# 5V_Buck_Boost_Converter.net
KiCad netlist of a schematic drawn in Altium Designer
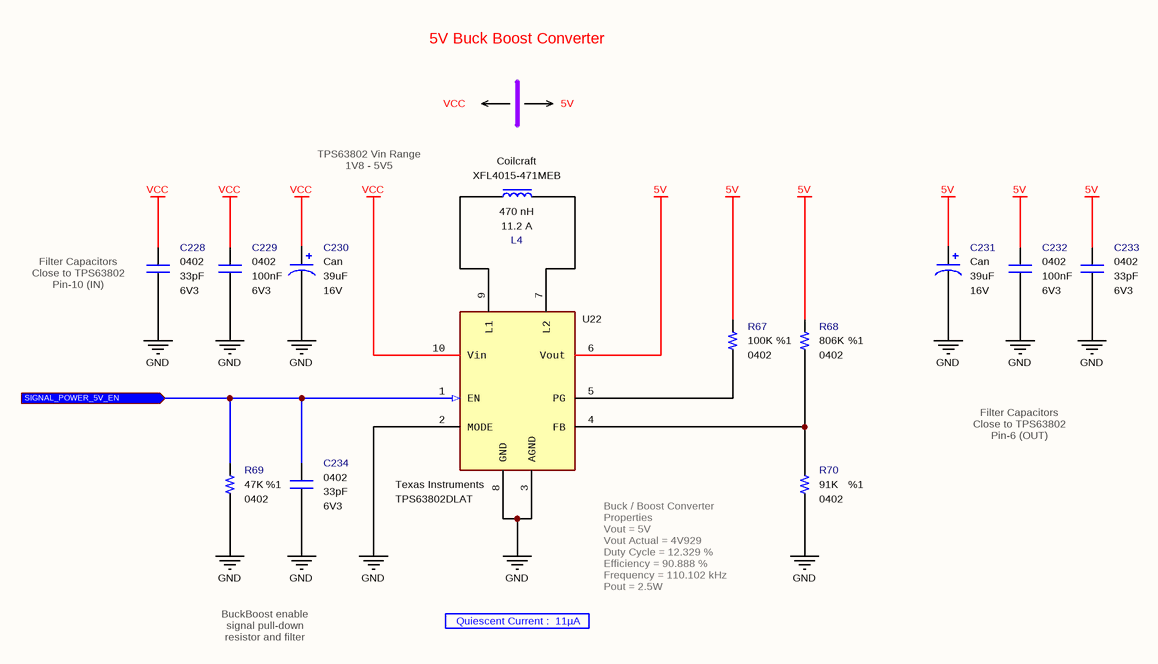
[diagram p0: 5V Buck Boost Converter.SchDoc]

(export (version "E")
  (design (tool "Eeschema 10.0.6"))
  (components
    (comp (ref "C228")
      (value "33pF")
      (footprint "CAPACITOR_0402")
      (description "Capacitor - 33pF [0402] (Ceramic)")
      (fields
        (field (name "TOLERANCE") "10%")
        (field (name "CASE") "0402")
        (field (name "VOLTAGE") "6V3")
        (field (name "MANUFACTURER PART NUMBER") "C0402C330J9RACAUTO")
      )
      (libsource (lib "Ovoo_Library") (part "Capacitor - 33pF [0402-6V3]"))
    )
    (comp (ref "C229")
      (value "100nF")
      (footprint "CAPACITOR_0402")
      (description "Capacitor - 100nF [0402-6V3] (Ceramic)")
      (fields
        (field (name "CASE") "0402")
        (field (name "TOLERANCE") "%10")
        (field (name "VOLTAGE") "6V3")
        (field (name "MANUFACTURER PART NUMBER") "04026D104KAT4A")
      )
      (libsource (lib "Ovoo_Library") (part "Capacitor - 100nF [0402-6V3]"))
    )
    (comp (ref "C230")
      (value "39uF")
      (footprint "CAPACITOR_CAN-B6")
      (description "Capacitor - 39uF 16V [Can] (Electrolytic)")
      (fields
        (field (name "TOLERANCE") "20%")
        (field (name "CASE") "Can")
        (field (name "VOLTAGE") "16V")
        (field (name "MANUFACTURER PART NUMBER") "16SVPC39MV")
      )
      (libsource (lib "Ovoo_Library") (part "Capacitor - 39uF [Can-16V]"))
    )
    (comp (ref "C231")
      (value "39uF")
      (footprint "CAPACITOR_CAN-B6")
      (description "Capacitor - 39uF 16V [Can] (Electrolytic)")
      (fields
        (field (name "TOLERANCE") "20%")
        (field (name "CASE") "Can")
        (field (name "VOLTAGE") "16V")
        (field (name "MANUFACTURER PART NUMBER") "16SVPC39MV")
      )
      (libsource (lib "Ovoo_Library") (part "Capacitor - 39uF [Can-16V]"))
    )
    (comp (ref "C232")
      (value "100nF")
      (footprint "CAPACITOR_0402")
      (description "Capacitor - 100nF [0402-6V3] (Ceramic)")
      (fields
        (field (name "CASE") "0402")
        (field (name "TOLERANCE") "%10")
        (field (name "VOLTAGE") "6V3")
        (field (name "MANUFACTURER PART NUMBER") "04026D104KAT4A")
      )
      (libsource (lib "Ovoo_Library") (part "Capacitor - 100nF [0402-6V3]"))
    )
    (comp (ref "C233")
      (value "33pF")
      (footprint "CAPACITOR_0402")
      (description "Capacitor - 33pF [0402] (Ceramic)")
      (fields
        (field (name "TOLERANCE") "10%")
        (field (name "CASE") "0402")
        (field (name "VOLTAGE") "6V3")
        (field (name "MANUFACTURER PART NUMBER") "C0402C330J9RACAUTO")
      )
      (libsource (lib "Ovoo_Library") (part "Capacitor - 33pF [0402-6V3]"))
    )
    (comp (ref "C234")
      (value "33pF")
      (footprint "CAPACITOR_0402")
      (description "Capacitor - 33pF [0402] (Ceramic)")
      (fields
        (field (name "TOLERANCE") "10%")
        (field (name "CASE") "0402")
        (field (name "VOLTAGE") "6V3")
        (field (name "MANUFACTURER PART NUMBER") "C0402C330J9RACAUTO")
      )
      (libsource (lib "Ovoo_Library") (part "Capacitor - 33pF [0402-6V3]"))
    )
    (comp (ref "L4")
      (value "470 nH")
      (footprint "INDUCTOR_XFL4015")
      (description "Fixed Inductors 0.47uH 20% 11.2A 8.36mOhms AEC-Q200")
      (fields
        (field (name "TOLERANCE") "20%")
        (field (name "MAXIMUM DC CURRENT") "11.2 A")
        (field (name "MOUSER PART NUMBER") "994-XFL4015-471MEB")
        (field (name "MANUFACTURER PART NUMBER") "XFL4015-471MEB")
        (field (name "MANUFACTURER NAME") "Coilcraft")
      )
      (libsource (lib "Ovoo_Library") (part "Inductor - 470 nH [SMD]"))
    )
    (comp (ref "R67")
      (value "100K")
      (footprint "RESISTOR_0402")
      (description "Thick Film Resistors - SMD 1/16 W 100 Kohms 1%")
      (fields
        (field (name "TOLERANCE") "%1")
        (field (name "CASE") "0402")
        (field (name "MANUFACTURER PART NUMBER") "CRCW0402100KFKED")
        (field (name "MOUSER PART NUMBER") "71-CRCW0402-100K-E3")
      )
      (libsource (lib "Ovoo_Library") (part "Resistor - 100K"))
    )
    (comp (ref "R68")
      (value "806K")
      (footprint "RESISTOR_0402")
      (description "Thick Film Resistors - SMD 1/16 W 806 Kohms 1%")
      (fields
        (field (name "TOLERANCE") "%1")
        (field (name "CASE") "0402")
        (field (name "MANUFACTURER PART NUMBER") "CRCW0402806KFKED")
        (field (name "MOUSER PART NUMBER") "71-CRCW0402-806K-E3")
      )
      (libsource (lib "Ovoo_Library") (part "Resistor - 806K"))
    )
    (comp (ref "R69")
      (value "47K")
      (footprint "RESISTOR_0402")
      (description "Thick Film Resistors - SMD 1/16 W 47 Kohms 1%")
      (fields
        (field (name "TOLERANCE") "%1")
        (field (name "CASE") "0402")
        (field (name "MANUFACTURER PART NUMBER") "CRCW040247K0FKED")
        (field (name "MOUSER PART NUMBER") "71-CRCW0402-47K-E3")
      )
      (libsource (lib "Ovoo_Library") (part "Resistor - 47K"))
    )
    (comp (ref "R70")
      (value "91K")
      (footprint "RESISTOR_0402")
      (description "Thick Film Resistors - SMD 1/16 W 91 Kohms 1%")
      (fields
        (field (name "TOLERANCE") "%1")
        (field (name "CASE") "0402")
        (field (name "MANUFACTURER PART NUMBER") "CRCW040291K0FKED")
        (field (name "MOUSER PART NUMBER") "71-CRCW040291K0FKED")
      )
      (libsource (lib "Ovoo_Library") (part "Resistor - 91K"))
    )
    (comp (ref "U22")
      (value "Buck-Boost Converter")
      (footprint "VSON-10")
      (fields
        (field (name "MOUSER PART NUMBER") "595-TPS63802DLAT")
        (field (name "MANUFACTURER PART NUMBER") "TPS63802DLAT")
        (field (name "MANUFACTURER NAME") "Texas Instruments")
      )
      (libsource (lib "Ovoo_Library") (part "IC - TPS63802DLAT"))
    )
  )
  (nets
    (net (code "1") (name "/SIGNAL_POWER_5V_EN") (class "Default")
      (node (ref "C234") (pin "2") (pinfunction "2_2") (pintype "passive"))
      (node (ref "R69") (pin "2") (pinfunction "2_2") (pintype "passive"))
      (node (ref "U22") (pin "1") (pinfunction "EN_1") (pintype "input"))
    )
    (net (code "2") (name "5V") (class "Default")
      (node (ref "C231") (pin "1") (pinfunction "1_1") (pintype "passive"))
      (node (ref "C232") (pin "1") (pinfunction "1_1") (pintype "passive"))
      (node (ref "C233") (pin "2") (pinfunction "2_2") (pintype "passive"))
      (node (ref "R67") (pin "2") (pinfunction "2_2") (pintype "passive"))
      (node (ref "R68") (pin "2") (pinfunction "2_2") (pintype "passive"))
      (node (ref "U22") (pin "6") (pinfunction "Vout_6") (pintype "power_in"))
    )
    (net (code "3") (name "GND") (class "Default")
      (node (ref "C228") (pin "1") (pinfunction "1_1") (pintype "passive"))
      (node (ref "C229") (pin "2") (pinfunction "2_2") (pintype "passive"))
      (node (ref "C230") (pin "2") (pinfunction "2_2") (pintype "passive"))
      (node (ref "C231") (pin "2") (pinfunction "2_2") (pintype "passive"))
      (node (ref "C232") (pin "2") (pinfunction "2_2") (pintype "passive"))
      (node (ref "C233") (pin "1") (pinfunction "1_1") (pintype "passive"))
      (node (ref "C234") (pin "1") (pinfunction "1_1") (pintype "passive"))
      (node (ref "R69") (pin "1") (pinfunction "1_1") (pintype "passive"))
      (node (ref "R70") (pin "1") (pinfunction "1_1") (pintype "passive"))
      (node (ref "U22") (pin "2") (pinfunction "MODE_2") (pintype "passive"))
      (node (ref "U22") (pin "3") (pinfunction "AGND_3") (pintype "power_in"))
      (node (ref "U22") (pin "8") (pinfunction "GND_8") (pintype "power_in"))
    )
    (net (code "4") (name "Net-(U22-FB)") (class "Default")
      (node (ref "R68") (pin "1") (pinfunction "1_1") (pintype "passive"))
      (node (ref "R70") (pin "2") (pinfunction "2_2") (pintype "passive"))
      (node (ref "U22") (pin "4") (pinfunction "FB_4") (pintype "passive"))
    )
    (net (code "5") (name "Net-(U22-L1)") (class "Default")
      (node (ref "L4") (pin "1") (pinfunction "1_1") (pintype "passive"))
      (node (ref "U22") (pin "9") (pinfunction "L1_9") (pintype "passive"))
    )
    (net (code "6") (name "Net-(U22-L2)") (class "Default")
      (node (ref "L4") (pin "2") (pinfunction "2_2") (pintype "passive"))
      (node (ref "U22") (pin "7") (pinfunction "L2_7") (pintype "passive"))
    )
    (net (code "7") (name "Net-(U22-PG)") (class "Default")
      (node (ref "R67") (pin "1") (pinfunction "1_1") (pintype "passive"))
      (node (ref "U22") (pin "5") (pinfunction "PG_5") (pintype "passive"))
    )
    (net (code "8") (name "VCC") (class "Default")
      (node (ref "C228") (pin "2") (pinfunction "2_2") (pintype "passive"))
      (node (ref "C229") (pin "1") (pinfunction "1_1") (pintype "passive"))
      (node (ref "C230") (pin "1") (pinfunction "1_1") (pintype "passive"))
      (node (ref "U22") (pin "10") (pinfunction "Vin_10") (pintype "power_in"))
    )
  )
)
